# Sch_front.net
KiCad netlist of a schematic drawn in Altium Designer
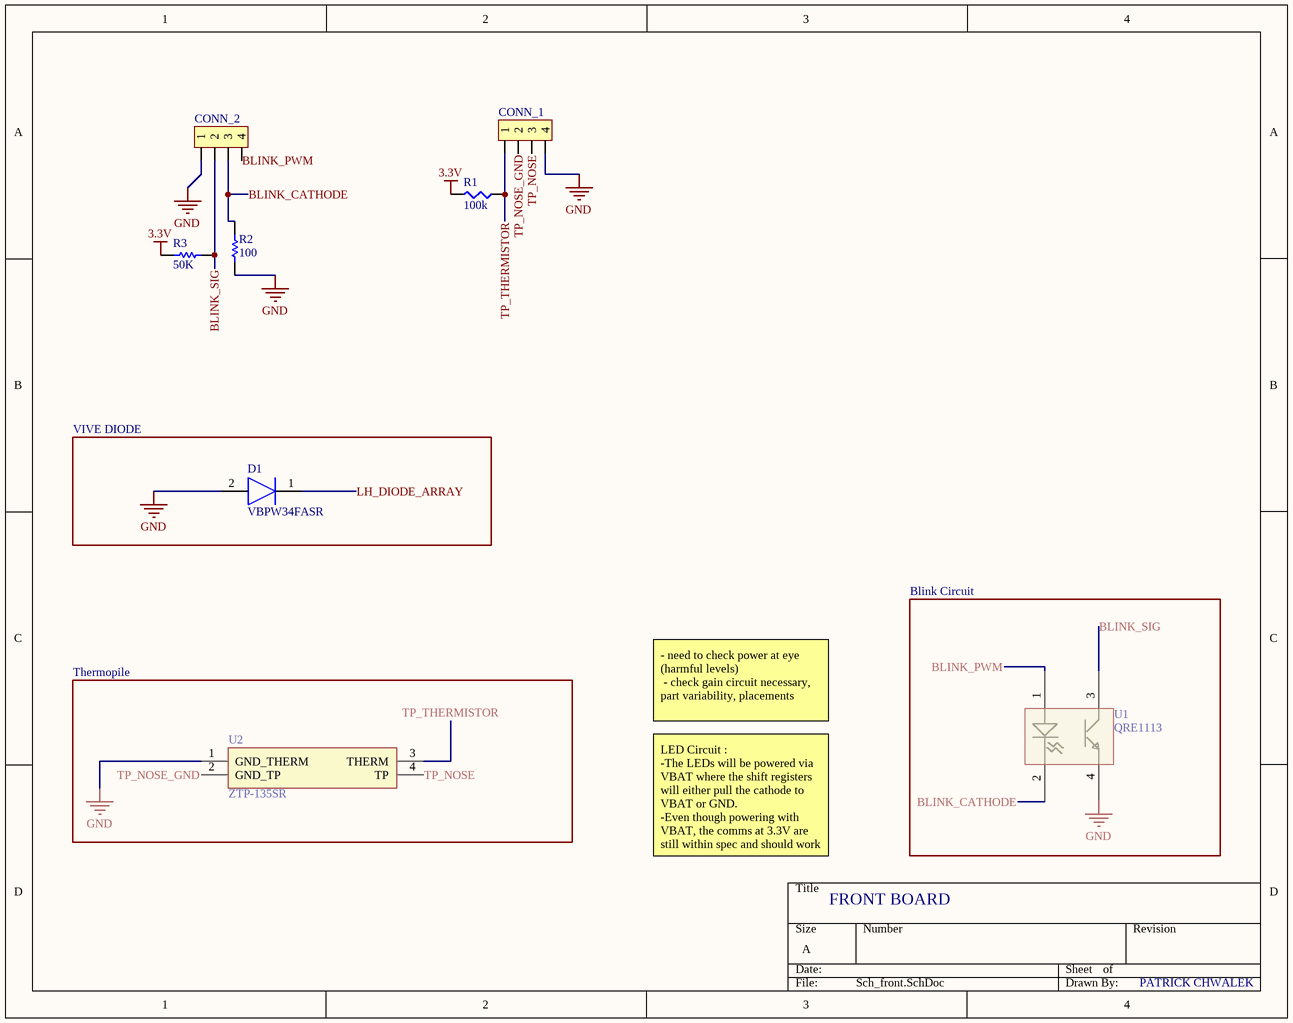
[diagram p0: Sch_front.SchDoc]

(export (version "E")
  (design (tool "Eeschema 10.0.6"))
  (components
    (comp (ref "CONN_1")
      (value "THERMO")
      (footprint "4_pos_1mm_header")
      (libsource (lib "schematic_components") (part "4_pin_1mm_header"))
    )
    (comp (ref "CONN_2")
      (value "BLINK")
      (footprint "4_pos_1mm_header")
      (libsource (lib "schematic_components") (part "4_pin_1mm_header"))
    )
    (comp (ref "D1")
      (value "VBPW34FASR")
      (footprint "VBPW34FAS")
      (description "Diode")
      (fields (field (name "MOUSER PART NUMBER") "782-VBPW34FASR") (field (name "RS PART NUMBER") "7689401"))
      (libsource (lib "*") (part "VBPW34FASR"))
    )
    (comp (ref "R1")
      (value "100k")
      (footprint "SMD-0402-RES")
      (description "RES SMD 100K OHM 5% 1/10W 0402")
      (fields (field (name "PART NUMBER") "ERJ-2GEJ104X") (field (name "DIGI-KEY PART NUMBER") "P100KJCT-ND"))
      (libsource (lib "Panasonic_ERJ_0402") (part "ERJ-2GEJ104X"))
    )
    (comp (ref "R2") (value "100") (footprint "0402R") (libsource (lib "bdm") (part "Resistor")))
    (comp (ref "R3") (value "50K") (footprint "0402R") (libsource (lib "bdm") (part "Resistor")))
    (comp (ref "U1")
      (value "QRE1113")
      (footprint "QRE1113_DIP")
      (description "IR Emitter and Receiver")
      (libsource (lib "Schematic Components") (part "QRE1113"))
    )
    (comp (ref "U2")
      (value "ZTP-135SR")
      (footprint "ZTP-135SR")
      (description "Undefined or Miscellaneous")
      (fields (field (name "MOUSER PART NUMBER") "527-ZTP-135SR"))
      (libsource (lib "SamacSys") (part "ZTP-135SR"))
    )
  )
  (nets
    (net (code "1") (name "/BLINK_CATHODE") (class "Default")
      (node (ref "CONN_2") (pin "3") (pinfunction "3_3") (pintype "passive"))
      (node (ref "R2") (pin "2") (pinfunction "2_2") (pintype "passive"))
      (node (ref "U1") (pin "2") (pinfunction "2_2") (pintype "passive"))
    )
    (net (code "2") (name "/BLINK_PWM") (class "Default")
      (node (ref "CONN_2") (pin "4") (pinfunction "4_4") (pintype "passive"))
      (node (ref "U1") (pin "1") (pinfunction "1_1") (pintype "passive"))
    )
    (net (code "3") (name "/BLINK_SIG") (class "Default")
      (node (ref "CONN_2") (pin "2") (pinfunction "2_2") (pintype "passive"))
      (node (ref "R3") (pin "1") (pinfunction "1_1") (pintype "passive"))
      (node (ref "U1") (pin "3") (pinfunction "3_3") (pintype "passive"))
    )
    (net (code "4") (name "/LH_DIODE_ARRAY") (class "Default")
      (node (ref "D1") (pin "1") (pinfunction "A_1") (pintype "passive"))
    )
    (net (code "5") (name "/TP_NOSE") (class "Default")
      (node (ref "CONN_1") (pin "3") (pinfunction "3_3") (pintype "passive"))
      (node (ref "U2") (pin "4") (pinfunction "TP_4") (pintype "passive"))
    )
    (net (code "6") (name "/TP_NOSE_GND") (class "Default")
      (node (ref "CONN_1") (pin "2") (pinfunction "2_2") (pintype "passive"))
      (node (ref "U2") (pin "2") (pinfunction "GND_TP_2") (pintype "passive"))
    )
    (net (code "7") (name "/TP_THERMISTOR") (class "Default")
      (node (ref "CONN_1") (pin "1") (pinfunction "1_1") (pintype "passive"))
      (node (ref "R1") (pin "1") (pinfunction "1_1") (pintype "passive"))
      (node (ref "U2") (pin "3") (pinfunction "THERM_3") (pintype "passive"))
    )
    (net (code "8") (name "3.3V") (class "Default")
      (node (ref "R1") (pin "2") (pinfunction "2_2") (pintype "passive"))
      (node (ref "R3") (pin "2") (pinfunction "2_2") (pintype "passive"))
    )
    (net (code "9") (name "GND") (class "Default")
      (node (ref "CONN_1") (pin "4") (pinfunction "4_4") (pintype "passive"))
      (node (ref "CONN_2") (pin "1") (pinfunction "1_1") (pintype "passive"))
      (node (ref "D1") (pin "2") (pinfunction "K_2") (pintype "passive"))
      (node (ref "R2") (pin "1") (pinfunction "1_1") (pintype "passive"))
      (node (ref "U1") (pin "4") (pinfunction "4_4") (pintype "passive"))
      (node (ref "U2") (pin "1") (pinfunction "GND_THERM_1") (pintype "passive"))
    )
  )
)
